# Circuit.net
KiCad netlist of a schematic drawn in Altium Designer
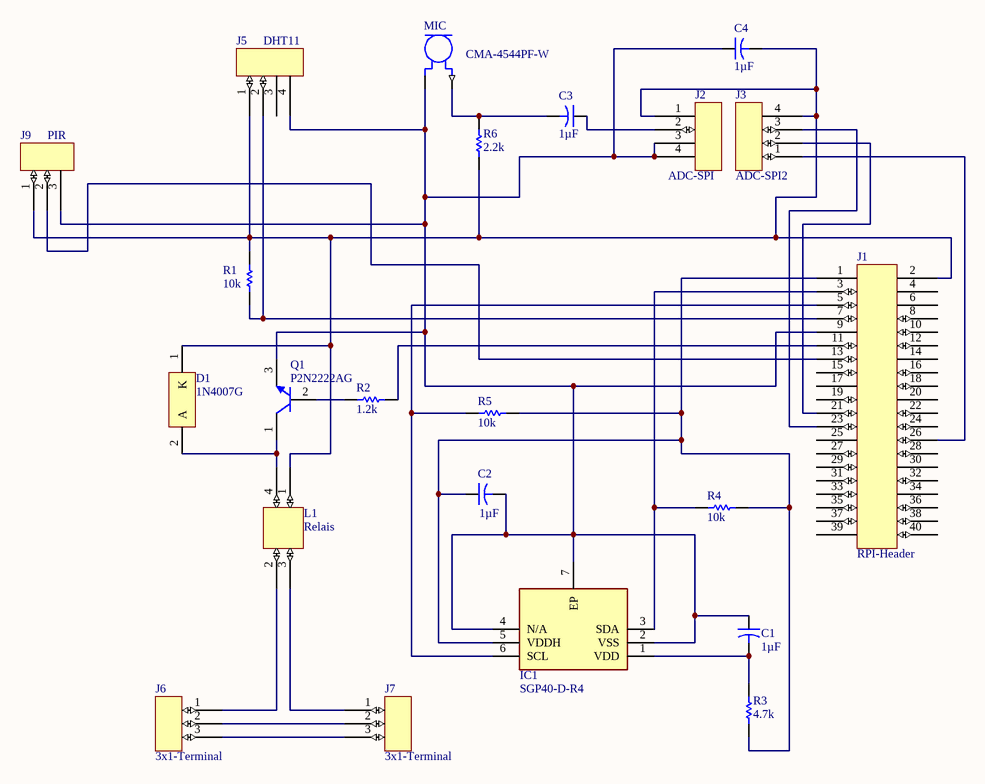
[diagram p0: Circuit.SchDoc]

(export (version "E")
  (design (tool "Eeschema 10.0.6"))
  (components
    (comp (ref "C1")
      (value "1µF")
      (footprint "CAPR5-4X5")
      (description "Capacitor")
      (fields (field (name "PUBLISHER") "Altium Limited"))
      (libsource (lib "Miscellaneous Devices") (part "Cap2"))
    )
    (comp (ref "C2")
      (value "1µF")
      (footprint "CAPR5-4X5")
      (description "Capacitor")
      (fields (field (name "Comment") "Cap2") (field (name "PUBLISHER") "Altium Limited"))
      (libsource (lib "Miscellaneous Devices") (part "Cap2"))
    )
    (comp (ref "C3")
      (value "1µF")
      (footprint "CAPR5-4X5")
      (description "Capacitor")
      (fields (field (name "PUBLISHER") "Altium Limited"))
      (libsource (lib "Miscellaneous Devices") (part "Cap2"))
    )
    (comp (ref "C4")
      (value "1µF")
      (footprint "CAPR5-4X5")
      (description "Capacitor")
      (fields (field (name "PUBLISHER") "Altium Limited"))
      (libsource (lib "Miscellaneous Devices") (part "Cap2"))
    )
    (comp (ref "D1")
      (value "1N4007G")
      (footprint "ONSC-AXIAL_LEAD-2-59-10_P")
      (description "Standard Recovery Rectifier, 2-Pin Axial_Lead, Pb-Free, Bulk Bag")
      (fields (field (name "MANUFACTURER") "On Semiconductor"))
      (libsource (lib "Altium Content Vault") (part "ONSC-D-K1A2-2_A"))
    )
    (comp (ref "IC1")
      (value "SGP40-D-R4")
      (footprint "SamacSys:SON80P244X244X95-7N")
      (description "Integrated Circuit")
      (fields (field (name "MOUSER PART NUMBER") "403-SGP40-D-R4"))
      (libsource (lib "*") (part "SGP40-D-R4"))
    )
    (comp (ref "J1")
      (value "RPI-Header")
      (footprint "RPI-Header")
      (libsource (lib "RPI-Header") (part "RPI-Header"))
    )
    (comp (ref "J2") (value "ADC-SPI") (footprint "4x1") (libsource (lib "") (part "4x1_1")))
    (comp (ref "J3") (value "ADC-SPI2") (footprint "4x1") (libsource (lib "Schlib1") (part "4x1")))
    (comp (ref "J5") (value "DHT11") (footprint "4x1") (libsource (lib "4x1") (part "4x1")))
    (comp (ref "J6")
      (value "3x1-Terminal")
      (footprint "3x1-Terminal")
      (libsource (lib "") (part "3x1-Terminal_1"))
    )
    (comp (ref "J7")
      (value "3x1-Terminal")
      (footprint "3x1-Terminal")
      (libsource (lib "3x1-Terminal") (part "3x1-Terminal"))
    )
    (comp (ref "J9") (value "PIR") (footprint "3x1") (libsource (lib "3x1") (part "3x1")))
    (comp (ref "L1") (value "Relais") (footprint "Relais") (libsource (lib "Relais") (part "Relais")))
    (comp (ref "MIC")
      (value "CMA-4544PF-W")
      (footprint "MIC_CMA-4544PF-W")
      (description "CMA Series 9.7 mm Electret Condenser Omni-Directional Pin Mount 3 V Microphone")
      (libsource (lib "CMA-4544PF-W") (part "CMA-4544PF-W"))
    )
    (comp (ref "Q1")
      (value "P2N2222AG")
      (footprint "ONSC-TO-92-3-29-11")
      (description "Amplifier Transistor, NPN Silicon, 3-Pin TO-92, Pb-Free, Bulk Box")
      (fields (field (name "MANUFACTURER") "On Semiconductor"))
      (libsource (lib "Altium Content Vault") (part "ONSC-NPN-C1B2E3-3"))
    )
    (comp (ref "R1")
      (value "10k")
      (footprint "AXIAL-0.3")
      (description "Resistor")
      (fields (field (name "PUBLISHER") "Altium Limited"))
      (libsource (lib "Miscellaneous Devices") (part "Res1"))
    )
    (comp (ref "R2")
      (value "1.2k")
      (footprint "AXIAL-0.3")
      (description "Resistor")
      (fields (field (name "PUBLISHER") "Altium Limited"))
      (libsource (lib "Miscellaneous Devices") (part "Res1"))
    )
    (comp (ref "R3")
      (value "4.7k")
      (footprint "AXIAL-0.3")
      (description "Resistor")
      (fields (field (name "PUBLISHER") "Altium Limited"))
      (libsource (lib "Miscellaneous Devices") (part "Res1"))
    )
    (comp (ref "R4")
      (value "10k")
      (footprint "AXIAL-0.3")
      (description "Resistor")
      (fields (field (name "PUBLISHER") "Altium Limited"))
      (libsource (lib "Miscellaneous Devices") (part "Res1"))
    )
    (comp (ref "R5")
      (value "10k")
      (footprint "AXIAL-0.3")
      (description "Resistor")
      (fields (field (name "PUBLISHER") "Altium Limited"))
      (libsource (lib "Miscellaneous Devices") (part "Res1"))
    )
    (comp (ref "R6")
      (value "2.2k")
      (footprint "AXIAL-0.3")
      (description "Resistor")
      (fields (field (name "PUBLISHER") "Altium Limited"))
      (libsource (lib "Miscellaneous Devices") (part "Res1"))
    )
  )
  (nets
    (net (code "1") (name "Net-(C3-Pad1)") (class "Default")
      (node (ref "C3") (pin "1") (pinfunction "1_1") (pintype "passive"))
      (node (ref "J2") (pin "2") (pintype "bidirectional"))
    )
    (net (code "2") (name "Net-(D1-A)") (class "Default")
      (node (ref "D1") (pin "2") (pinfunction "A_2") (pintype "passive"))
      (node (ref "L1") (pin "4") (pintype "bidirectional"))
      (node (ref "Q1") (pin "1") (pinfunction "C_1") (pintype "passive"))
    )
    (net (code "3") (name "Net-(D1-K)") (class "Default")
      (node (ref "C4") (pin "2") (pinfunction "2_2") (pintype "passive"))
      (node (ref "D1") (pin "1") (pinfunction "K_1") (pintype "passive"))
      (node (ref "J1") (pin "2") (pintype "passive"))
      (node (ref "J2") (pin "1") (pintype "passive"))
      (node (ref "J3") (pin "4") (pintype "passive"))
      (node (ref "J5") (pin "1") (pintype "bidirectional"))
      (node (ref "J9") (pin "1") (pintype "bidirectional"))
      (node (ref "L1") (pin "1") (pintype "bidirectional"))
      (node (ref "R1") (pin "1") (pinfunction "1_1") (pintype "passive"))
      (node (ref "R6") (pin "1") (pinfunction "1_1") (pintype "passive"))
    )
    (net (code "4") (name "Net-(IC1-EP)") (class "Default")
      (node (ref "C1") (pin "1") (pinfunction "1_1") (pintype "passive"))
      (node (ref "C2") (pin "2") (pinfunction "2_2") (pintype "passive"))
      (node (ref "C4") (pin "1") (pinfunction "1_1") (pintype "passive"))
      (node (ref "IC1") (pin "2") (pinfunction "VSS_2") (pintype "passive"))
      (node (ref "IC1") (pin "4") (pinfunction "N/A_4") (pintype "passive"))
      (node (ref "IC1") (pin "7") (pinfunction "EP_7") (pintype "passive"))
      (node (ref "J1") (pin "9") (pintype "passive"))
      (node (ref "J2") (pin "3") (pintype "passive"))
      (node (ref "J2") (pin "4") (pintype "passive"))
      (node (ref "J5") (pin "4") (pintype "passive"))
      (node (ref "J9") (pin "3") (pintype "passive"))
      (node (ref "MIC") (pin "2") (pinfunction "GND_2") (pintype "power_in"))
      (node (ref "Q1") (pin "3") (pinfunction "E_3") (pintype "passive"))
    )
    (net (code "5") (name "Net-(IC1-SCL)") (class "Default")
      (node (ref "IC1") (pin "6") (pinfunction "SCL_6") (pintype "passive"))
      (node (ref "J1") (pin "5") (pintype "bidirectional"))
      (node (ref "R5") (pin "1") (pinfunction "1_1") (pintype "passive"))
    )
    (net (code "6") (name "Net-(IC1-SDA)") (class "Default")
      (node (ref "IC1") (pin "3") (pinfunction "SDA_3") (pintype "passive"))
      (node (ref "J1") (pin "3") (pintype "bidirectional"))
      (node (ref "R4") (pin "1") (pinfunction "1_1") (pintype "passive"))
    )
    (net (code "7") (name "Net-(IC1-VDD)") (class "Default")
      (node (ref "C1") (pin "2") (pinfunction "2_2") (pintype "passive"))
      (node (ref "IC1") (pin "1") (pinfunction "VDD_1") (pintype "passive"))
      (node (ref "R3") (pin "2") (pinfunction "2_2") (pintype "passive"))
    )
    (net (code "8") (name "Net-(IC1-VDDH)") (class "Default")
      (node (ref "C2") (pin "1") (pinfunction "1_1") (pintype "passive"))
      (node (ref "IC1") (pin "5") (pinfunction "VDDH_5") (pintype "passive"))
      (node (ref "J1") (pin "1") (pintype "passive"))
      (node (ref "R3") (pin "1") (pinfunction "1_1") (pintype "passive"))
      (node (ref "R4") (pin "2") (pinfunction "2_2") (pintype "passive"))
      (node (ref "R5") (pin "2") (pinfunction "2_2") (pintype "passive"))
    )
    (net (code "9") (name "Net-(J1-Pad7)") (class "Default")
      (node (ref "J1") (pin "7") (pintype "bidirectional"))
      (node (ref "J5") (pin "2") (pintype "bidirectional"))
      (node (ref "R1") (pin "2") (pinfunction "2_2") (pintype "passive"))
    )
    (net (code "10") (name "Net-(J1-Pad11)") (class "Default")
      (node (ref "J1") (pin "11") (pintype "bidirectional"))
      (node (ref "R2") (pin "2") (pinfunction "2_2") (pintype "passive"))
    )
    (net (code "11") (name "Net-(J1-Pad13)") (class "Default")
      (node (ref "J1") (pin "13") (pintype "bidirectional"))
      (node (ref "J9") (pin "2") (pintype "bidirectional"))
    )
    (net (code "12") (name "Net-(J1-Pad21)") (class "Default")
      (node (ref "J1") (pin "21") (pintype "bidirectional"))
      (node (ref "J3") (pin "2") (pintype "bidirectional"))
    )
    (net (code "13") (name "Net-(J1-Pad23)") (class "Default")
      (node (ref "J1") (pin "23") (pintype "bidirectional"))
      (node (ref "J3") (pin "3") (pintype "bidirectional"))
    )
    (net (code "14") (name "Net-(J1-Pad26)") (class "Default")
      (node (ref "J1") (pin "26") (pintype "bidirectional"))
      (node (ref "J3") (pin "1") (pintype "bidirectional"))
    )
    (net (code "15") (name "Net-(J6-Pad1)") (class "Default")
      (node (ref "J6") (pin "1") (pintype "bidirectional"))
      (node (ref "L1") (pin "2") (pintype "bidirectional"))
    )
    (net (code "16") (name "Net-(J6-Pad2)") (class "Default")
      (node (ref "J6") (pin "2") (pintype "bidirectional"))
      (node (ref "J7") (pin "2") (pintype "bidirectional"))
    )
    (net (code "17") (name "Net-(J6-Pad3)") (class "Default")
      (node (ref "J6") (pin "3") (pintype "bidirectional"))
      (node (ref "J7") (pin "3") (pintype "bidirectional"))
    )
    (net (code "18") (name "Net-(J7-Pad1)") (class "Default")
      (node (ref "J7") (pin "1") (pintype "bidirectional"))
      (node (ref "L1") (pin "3") (pintype "bidirectional"))
    )
    (net (code "19") (name "Net-(MIC-OUT)") (class "Default")
      (node (ref "C3") (pin "2") (pinfunction "2_2") (pintype "passive"))
      (node (ref "MIC") (pin "1") (pinfunction "OUT_1") (pintype "output"))
      (node (ref "R6") (pin "2") (pinfunction "2_2") (pintype "passive"))
    )
    (net (code "20") (name "Net-(Q1-B)") (class "Default")
      (node (ref "Q1") (pin "2") (pinfunction "B_2") (pintype "passive"))
      (node (ref "R2") (pin "1") (pinfunction "1_1") (pintype "passive"))
    )
    (net (code "21") (name "unconnected-(J1-Pad4)") (class "Default")
      (node (ref "J1") (pin "4") (pintype "passive"))
    )
    (net (code "22") (name "unconnected-(J1-Pad6)") (class "Default")
      (node (ref "J1") (pin "6") (pintype "passive"))
    )
    (net (code "23") (name "unconnected-(J1-Pad8)") (class "Default")
      (node (ref "J1") (pin "8") (pintype "bidirectional"))
    )
    (net (code "24") (name "unconnected-(J1-Pad10)") (class "Default")
      (node (ref "J1") (pin "10") (pintype "bidirectional"))
    )
    (net (code "25") (name "unconnected-(J1-Pad12)") (class "Default")
      (node (ref "J1") (pin "12") (pintype "bidirectional"))
    )
    (net (code "26") (name "unconnected-(J1-Pad14)") (class "Default")
      (node (ref "J1") (pin "14") (pintype "passive"))
    )
    (net (code "27") (name "unconnected-(J1-Pad15)") (class "Default")
      (node (ref "J1") (pin "15") (pintype "bidirectional"))
    )
    (net (code "28") (name "unconnected-(J1-Pad16)") (class "Default")
      (node (ref "J1") (pin "16") (pintype "bidirectional"))
    )
    (net (code "29") (name "unconnected-(J1-Pad17)") (class "Default")
      (node (ref "J1") (pin "17") (pintype "passive"))
    )
    (net (code "30") (name "unconnected-(J1-Pad18)") (class "Default")
      (node (ref "J1") (pin "18") (pintype "bidirectional"))
    )
    (net (code "31") (name "unconnected-(J1-Pad19)") (class "Default")
      (node (ref "J1") (pin "19") (pintype "bidirectional"))
    )
    (net (code "32") (name "unconnected-(J1-Pad20)") (class "Default")
      (node (ref "J1") (pin "20") (pintype "passive"))
    )
    (net (code "33") (name "unconnected-(J1-Pad22)") (class "Default")
      (node (ref "J1") (pin "22") (pintype "bidirectional"))
    )
    (net (code "34") (name "unconnected-(J1-Pad24)") (class "Default")
      (node (ref "J1") (pin "24") (pintype "bidirectional"))
    )
    (net (code "35") (name "unconnected-(J1-Pad25)") (class "Default")
      (node (ref "J1") (pin "25") (pintype "passive"))
    )
    (net (code "36") (name "unconnected-(J1-Pad27)") (class "Default")
      (node (ref "J1") (pin "27") (pintype "bidirectional"))
    )
    (net (code "37") (name "unconnected-(J1-Pad28)") (class "Default")
      (node (ref "J1") (pin "28") (pintype "bidirectional"))
    )
    (net (code "38") (name "unconnected-(J1-Pad29)") (class "Default")
      (node (ref "J1") (pin "29") (pintype "bidirectional"))
    )
    (net (code "39") (name "unconnected-(J1-Pad30)") (class "Default")
      (node (ref "J1") (pin "30") (pintype "passive"))
    )
    (net (code "40") (name "unconnected-(J1-Pad31)") (class "Default")
      (node (ref "J1") (pin "31") (pintype "bidirectional"))
    )
    (net (code "41") (name "unconnected-(J1-Pad32)") (class "Default")
      (node (ref "J1") (pin "32") (pintype "bidirectional"))
    )
    (net (code "42") (name "unconnected-(J1-Pad33)") (class "Default")
      (node (ref "J1") (pin "33") (pintype "bidirectional"))
    )
    (net (code "43") (name "unconnected-(J1-Pad34)") (class "Default")
      (node (ref "J1") (pin "34") (pintype "passive"))
    )
    (net (code "44") (name "unconnected-(J1-Pad35)") (class "Default")
      (node (ref "J1") (pin "35") (pintype "bidirectional"))
    )
    (net (code "45") (name "unconnected-(J1-Pad36)") (class "Default")
      (node (ref "J1") (pin "36") (pintype "bidirectional"))
    )
    (net (code "46") (name "unconnected-(J1-Pad37)") (class "Default")
      (node (ref "J1") (pin "37") (pintype "bidirectional"))
    )
    (net (code "47") (name "unconnected-(J1-Pad38)") (class "Default")
      (node (ref "J1") (pin "38") (pintype "bidirectional"))
    )
    (net (code "48") (name "unconnected-(J1-Pad39)") (class "Default")
      (node (ref "J1") (pin "39") (pintype "passive"))
    )
    (net (code "49") (name "unconnected-(J1-Pad40)") (class "Default")
      (node (ref "J1") (pin "40") (pintype "bidirectional"))
    )
    (net (code "50") (name "unconnected-(J5-Pad3)") (class "Default")
      (node (ref "J5") (pin "3") (pintype "passive"))
    )
  )
)
